# Polarshield_v2_0.net
KiCad netlist of a schematic drawn in EAGLE
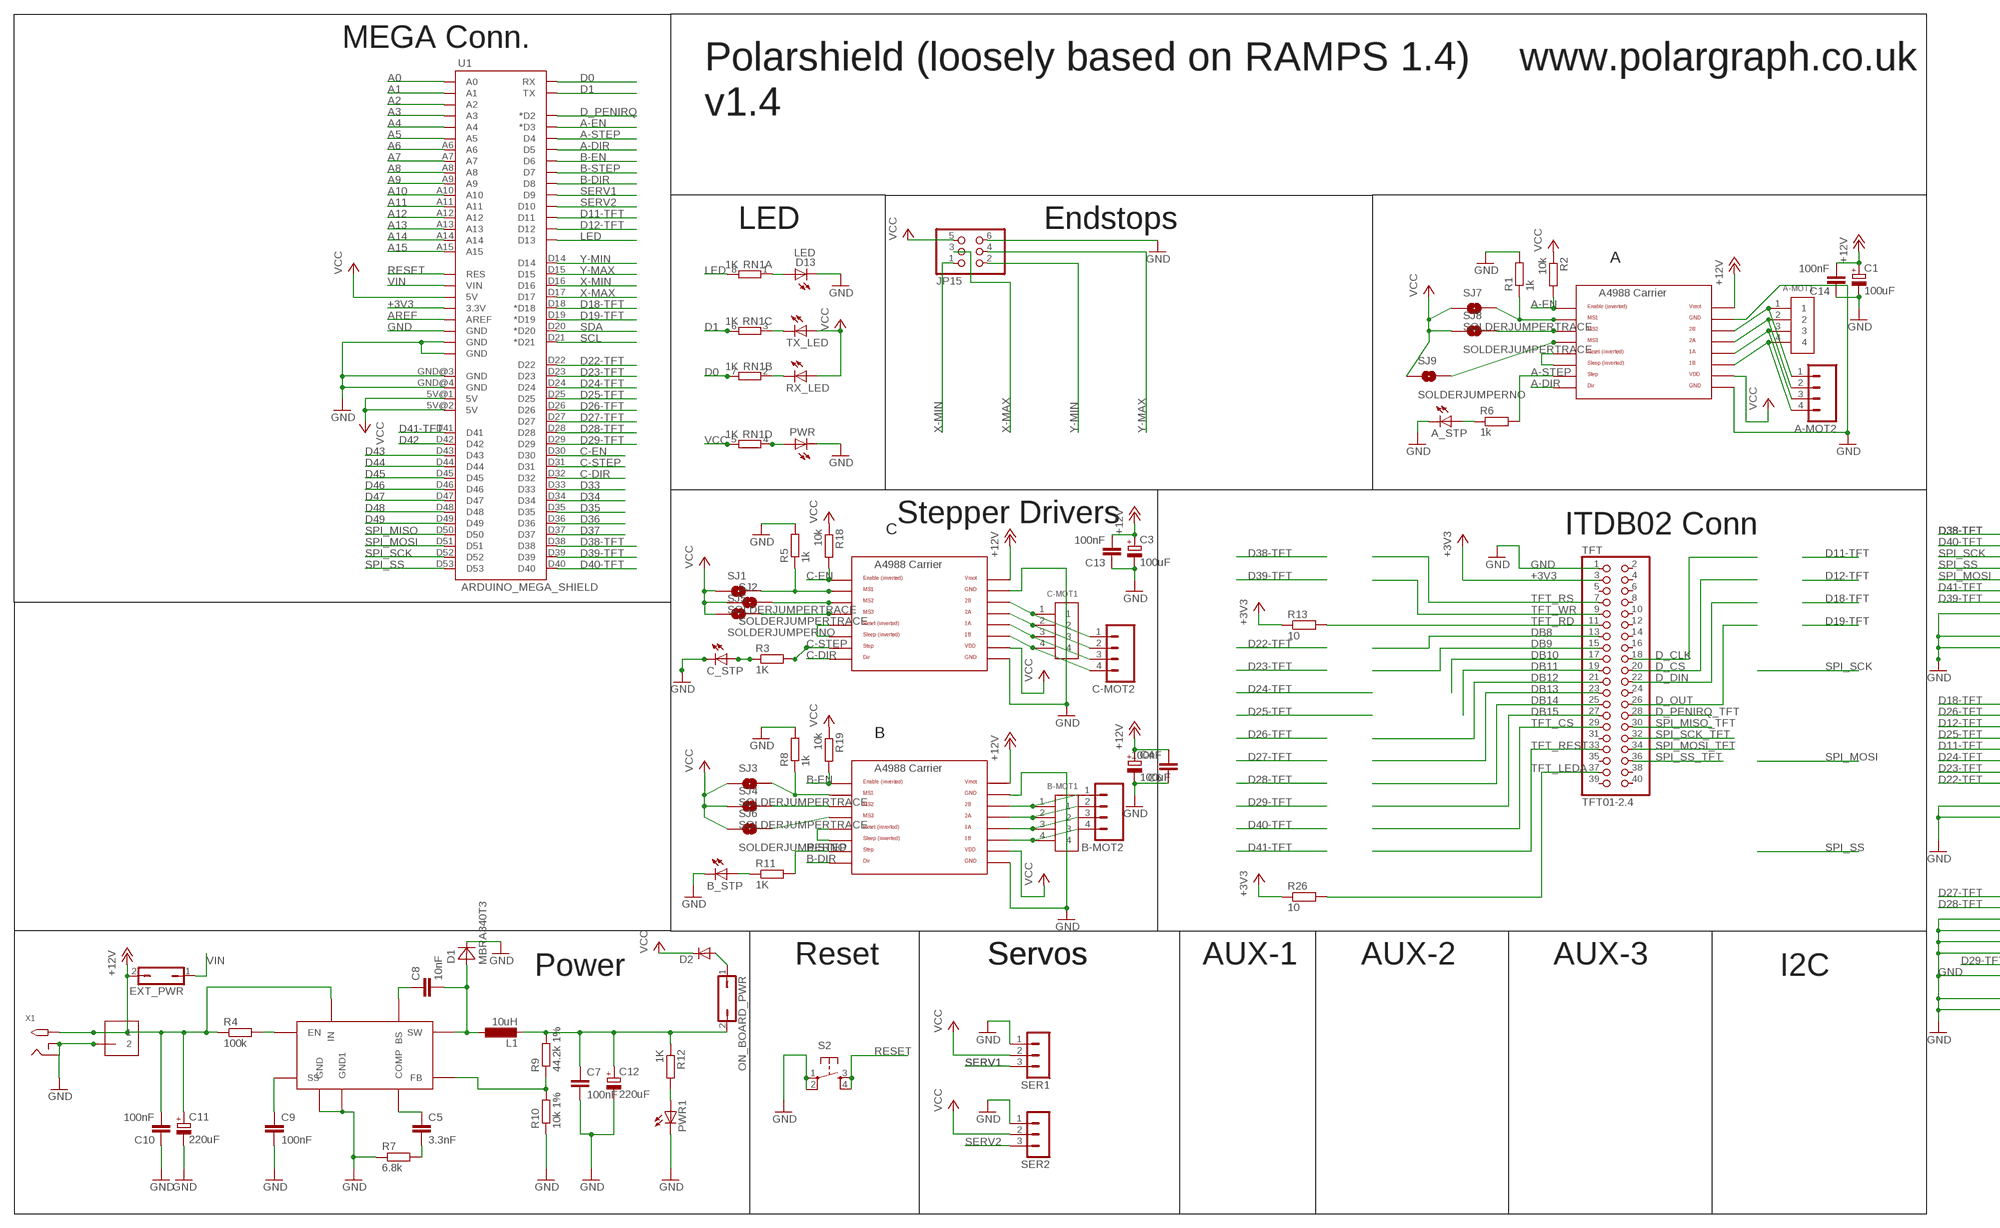
[diagram p0: schematic, sheet 1, part 1 of 2]
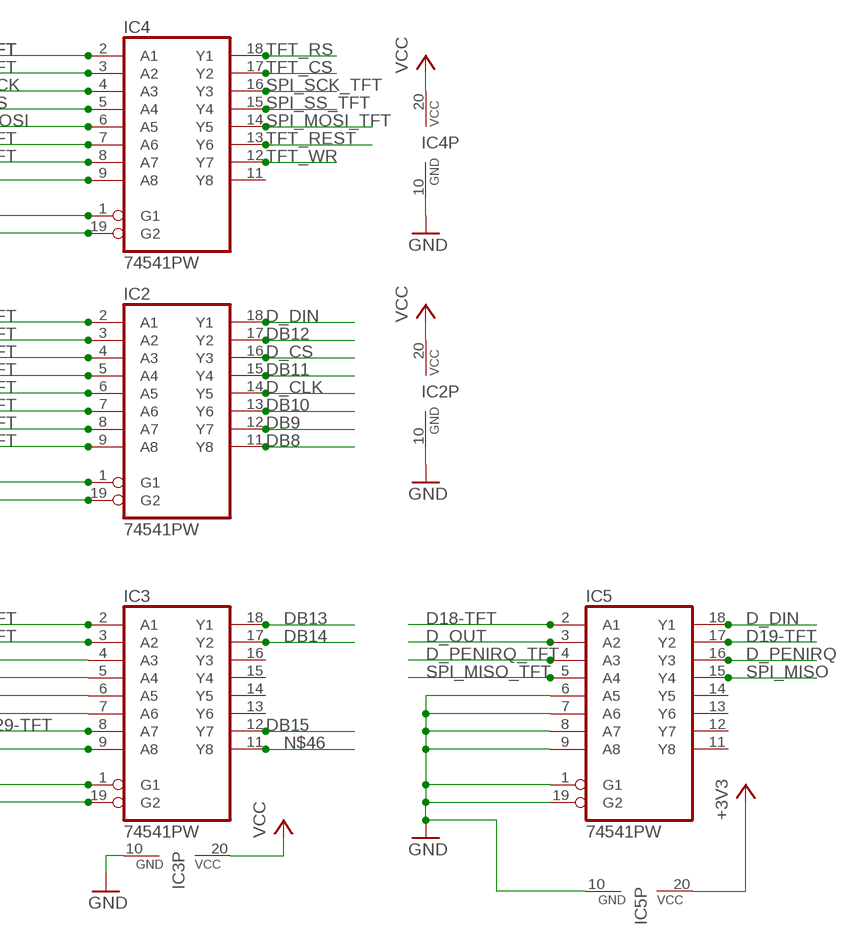
[diagram p1: schematic, sheet 1, part 2 of 2]

(export (version "E")
  (design (tool "Eeschema 10.0.6"))
  (components
    (comp (ref "A-MOT1")
      (value "1X4-BIG")
      (footprint "eagle-import:1X04-BIG")
      (libsource (lib "eagle-import") (part "1X4-BIG"))
    )
    (comp (ref "A-MOT2")
      (value "M04SCREW")
      (footprint "eagle-import:SCREWTERMINAL-3.5MM-4")
      (libsource (lib "eagle-import") (part "M04SCREW"))
    )
    (comp (ref "A_STP")
      (value "LEDCHIP-LED0805")
      (footprint "eagle-import:CHIP-LED0805")
      (libsource (lib "eagle-import") (part "LEDCHIP-LED0805"))
    )
    (comp (ref "B-MOT1")
      (value "1X4-BIG")
      (footprint "eagle-import:1X04-BIG")
      (libsource (lib "eagle-import") (part "1X4-BIG"))
    )
    (comp (ref "B-MOT2")
      (value "M04SCREW")
      (footprint "eagle-import:SCREWTERMINAL-3.5MM-4")
      (libsource (lib "eagle-import") (part "M04SCREW"))
    )
    (comp (ref "B_STP")
      (value "LEDCHIP-LED0805")
      (footprint "eagle-import:CHIP-LED0805")
      (libsource (lib "eagle-import") (part "LEDCHIP-LED0805"))
    )
    (comp (ref "C-MOT1")
      (value "1X4-BIG")
      (footprint "eagle-import:1X04-BIG")
      (libsource (lib "eagle-import") (part "1X4-BIG"))
    )
    (comp (ref "C-MOT2")
      (value "M04SCREW")
      (footprint "eagle-import:SCREWTERMINAL-3.5MM-4")
      (libsource (lib "eagle-import") (part "M04SCREW"))
    )
    (comp (ref "C1")
      (value "100uF")
      (footprint "eagle-import:153CLV-0605")
      (libsource (lib "eagle-import") (part "CPOL-EU153CLV-0605"))
    )
    (comp (ref "C3")
      (value "100uF")
      (footprint "eagle-import:153CLV-0605")
      (libsource (lib "eagle-import") (part "CPOL-EU153CLV-0605"))
    )
    (comp (ref "C4")
      (value "100uF")
      (footprint "eagle-import:153CLV-0605")
      (libsource (lib "eagle-import") (part "CPOL-EU153CLV-0605"))
    )
    (comp (ref "C5")
      (value "3.3nF")
      (footprint "eagle-import:C0805K")
      (libsource (lib "eagle-import") (part "C-EUC0805K"))
    )
    (comp (ref "C6")
      (value "100nF")
      (footprint "eagle-import:C0805")
      (libsource (lib "eagle-import") (part "C-EUC0805"))
    )
    (comp (ref "C7")
      (value "100nF")
      (footprint "eagle-import:C0805K")
      (libsource (lib "eagle-import") (part "C-EUC0805K"))
    )
    (comp (ref "C8")
      (value "10nF")
      (footprint "eagle-import:C0805K")
      (libsource (lib "eagle-import") (part "C-EUC0805K"))
    )
    (comp (ref "C9")
      (value "100nF")
      (footprint "eagle-import:C0805K")
      (libsource (lib "eagle-import") (part "C-EUC0805K"))
    )
    (comp (ref "C10")
      (value "100nF")
      (footprint "eagle-import:C0805K")
      (libsource (lib "eagle-import") (part "C-EUC0805K"))
    )
    (comp (ref "C11")
      (value "220uF")
      (footprint "eagle-import:153CLV-0807")
      (libsource (lib "eagle-import") (part "resistor_CPOL-EU153CLV-0807"))
    )
    (comp (ref "C12")
      (value "220uF")
      (footprint "eagle-import:153CLV-0807")
      (libsource (lib "eagle-import") (part "resistor_CPOL-EU153CLV-0807"))
    )
    (comp (ref "C13")
      (value "100nF")
      (footprint "eagle-import:C0805")
      (libsource (lib "eagle-import") (part "C-EUC0805"))
    )
    (comp (ref "C14")
      (value "100nF")
      (footprint "eagle-import:C0805")
      (libsource (lib "eagle-import") (part "C-EUC0805"))
    )
    (comp (ref "C_STP")
      (value "LEDCHIP-LED0805")
      (footprint "eagle-import:CHIP-LED0805")
      (libsource (lib "eagle-import") (part "LEDCHIP-LED0805"))
    )
    (comp (ref "D1")
      (value "MBRA340T3")
      (footprint "eagle-import:SMA")
      (libsource (lib "eagle-import") (part "MBRA340T3"))
    )
    (comp (ref "D2")
      (value "DIODE-DO214BA")
      (footprint "eagle-import:DO214BA")
      (libsource (lib "eagle-import") (part "DIODE-DO214BA"))
    )
    (comp (ref "D13")
      (value "LED")
      (footprint "eagle-import:CHIP-LED0805")
      (libsource (lib "eagle-import") (part "LEDCHIP-LED0805"))
    )
    (comp (ref "EXT_PWR")
      (value "JP1Q")
      (footprint "eagle-import:JP1")
      (libsource (lib "eagle-import") (part "JP1Q"))
    )
    (comp (ref "IC1")
      (value "MP2307")
      (footprint "eagle-import:SOIC8")
      (libsource (lib "eagle-import") (part "MP2307"))
    )
    (comp (ref "IC2")
      (value "74541PW")
      (footprint "eagle-import:TSSOP20")
      (libsource (lib "eagle-import") (part "74541PW"))
    )
    (comp (ref "IC3")
      (value "74541PW")
      (footprint "eagle-import:TSSOP20")
      (libsource (lib "eagle-import") (part "74541PW"))
    )
    (comp (ref "IC4")
      (value "74541PW")
      (footprint "eagle-import:TSSOP20")
      (libsource (lib "eagle-import") (part "74541PW"))
    )
    (comp (ref "IC5")
      (value "74541PW")
      (footprint "eagle-import:TSSOP20")
      (libsource (lib "eagle-import") (part "74541PW"))
    )
    (comp (ref "J1")
      (value "1X2-3.5MM")
      (footprint "eagle-import:1X2-3.5MM")
      (libsource (lib "eagle-import") (part "1X2-3.5MM"))
    )
    (comp (ref "JP15")
      (value "PINHD-2X3")
      (footprint "eagle-import:2X03")
      (libsource (lib "eagle-import") (part "PINHD-2X3"))
    )
    (comp (ref "L1")
      (value "10uH")
      (footprint "eagle-import:PIS2816")
      (libsource (lib "eagle-import") (part "L-EUPIS2816"))
    )
    (comp (ref "ON_BOARD_PWR")
      (value "JP1Q")
      (footprint "eagle-import:JP1")
      (libsource (lib "eagle-import") (part "JP1Q"))
    )
    (comp (ref "PWR")
      (value "LEDCHIP-LED0805")
      (footprint "eagle-import:CHIP-LED0805")
      (libsource (lib "eagle-import") (part "LEDCHIP-LED0805"))
    )
    (comp (ref "PWR1")
      (value "LEDCHIP-LED0805")
      (footprint "eagle-import:CHIP-LED0805")
      (libsource (lib "eagle-import") (part "LEDCHIP-LED0805"))
    )
    (comp (ref "R1")
      (value "1k")
      (footprint "eagle-import:R0805")
      (libsource (lib "eagle-import") (part "R-EU_R0805"))
    )
    (comp (ref "R2")
      (value "10k")
      (footprint "eagle-import:R0805")
      (libsource (lib "eagle-import") (part "R-EU_R0805"))
    )
    (comp (ref "R3")
      (value "1K")
      (footprint "eagle-import:R0805")
      (libsource (lib "eagle-import") (part "R-EU_R0805"))
    )
    (comp (ref "R4")
      (value "100k")
      (footprint "eagle-import:R0805")
      (libsource (lib "eagle-import") (part "resistor_R-EU_R0805"))
    )
    (comp (ref "R5")
      (value "1k")
      (footprint "eagle-import:R0805")
      (libsource (lib "eagle-import") (part "R-EU_R0805"))
    )
    (comp (ref "R6")
      (value "1k")
      (footprint "eagle-import:R0805")
      (libsource (lib "eagle-import") (part "R-EU_R0805"))
    )
    (comp (ref "R7")
      (value "6.8k")
      (footprint "eagle-import:R0805")
      (libsource (lib "eagle-import") (part "resistor_R-EU_R0805"))
    )
    (comp (ref "R8")
      (value "1k")
      (footprint "eagle-import:R0805")
      (libsource (lib "eagle-import") (part "R-EU_R0805"))
    )
    (comp (ref "R9")
      (value "44.2k 1%")
      (footprint "eagle-import:R0805")
      (libsource (lib "eagle-import") (part "resistor_R-EU_R0805"))
    )
    (comp (ref "R10")
      (value "10k 1%")
      (footprint "eagle-import:R0805")
      (libsource (lib "eagle-import") (part "resistor_R-EU_R0805"))
    )
    (comp (ref "R11")
      (value "1K")
      (footprint "eagle-import:R0805")
      (libsource (lib "eagle-import") (part "R-EU_R0805"))
    )
    (comp (ref "R12")
      (value "1K")
      (footprint "eagle-import:R0805")
      (libsource (lib "eagle-import") (part "R-EU_R0805"))
    )
    (comp (ref "R13")
      (value "10")
      (footprint "eagle-import:R0805")
      (libsource (lib "eagle-import") (part "resistor_R-EU_R0805"))
    )
    (comp (ref "R18")
      (value "10k")
      (footprint "eagle-import:R0805")
      (libsource (lib "eagle-import") (part "R-EU_R0805"))
    )
    (comp (ref "R19")
      (value "10k")
      (footprint "eagle-import:R0805")
      (libsource (lib "eagle-import") (part "R-EU_R0805"))
    )
    (comp (ref "R26")
      (value "10")
      (footprint "eagle-import:R0805")
      (libsource (lib "eagle-import") (part "resistor_R-EU_R0805"))
    )
    (comp (ref "RN1")
      (value "1K")
      (footprint "eagle-import:EXBS8V")
      (libsource (lib "eagle-import") (part "4R-NEXBS8V"))
    )
    (comp (ref "RX_LED")
      (value "LEDCHIP-LED0805")
      (footprint "eagle-import:CHIP-LED0805")
      (libsource (lib "eagle-import") (part "LEDCHIP-LED0805"))
    )
    (comp (ref "S2")
      (value "TAC_SWITCHPTH")
      (footprint "eagle-import:TACTILE-PTH")
      (libsource (lib "eagle-import") (part "TAC_SWITCHPTH"))
    )
    (comp (ref "SER1")
      (value "3PIN-HEADER")
      (footprint "eagle-import:3PIN-HEADER")
      (libsource (lib "eagle-import") (part "3PIN-HEADER"))
    )
    (comp (ref "SER2")
      (value "3PIN-HEADER")
      (footprint "eagle-import:3PIN-HEADER")
      (libsource (lib "eagle-import") (part "3PIN-HEADER"))
    )
    (comp (ref "SJ1")
      (value "SOLDERJUMPERTRACE")
      (footprint "eagle-import:SJ_2S-TRACE")
      (libsource (lib "eagle-import") (part "SOLDERJUMPERTRACE"))
    )
    (comp (ref "SJ2")
      (value "SOLDERJUMPERTRACE")
      (footprint "eagle-import:SJ_2S-TRACE")
      (libsource (lib "eagle-import") (part "SOLDERJUMPERTRACE"))
    )
    (comp (ref "SJ3")
      (value "SOLDERJUMPERTRACE")
      (footprint "eagle-import:SJ_2S-TRACE")
      (libsource (lib "eagle-import") (part "SOLDERJUMPERTRACE"))
    )
    (comp (ref "SJ4")
      (value "SOLDERJUMPERTRACE")
      (footprint "eagle-import:SJ_2S-TRACE")
      (libsource (lib "eagle-import") (part "SOLDERJUMPERTRACE"))
    )
    (comp (ref "SJ5")
      (value "SOLDERJUMPERNO")
      (footprint "eagle-import:SJ_2S-NO")
      (libsource (lib "eagle-import") (part "SOLDERJUMPERNO"))
    )
    (comp (ref "SJ6")
      (value "SOLDERJUMPERNO")
      (footprint "eagle-import:SJ_2S-NO")
      (libsource (lib "eagle-import") (part "SOLDERJUMPERNO"))
    )
    (comp (ref "SJ7")
      (value "SOLDERJUMPERTRACE")
      (footprint "eagle-import:SJ_2S-TRACE")
      (libsource (lib "eagle-import") (part "SOLDERJUMPERTRACE"))
    )
    (comp (ref "SJ8")
      (value "SOLDERJUMPERTRACE")
      (footprint "eagle-import:SJ_2S-TRACE")
      (libsource (lib "eagle-import") (part "SOLDERJUMPERTRACE"))
    )
    (comp (ref "SJ9")
      (value "SOLDERJUMPERNO")
      (footprint "eagle-import:SJ_2S-NO")
      (libsource (lib "eagle-import") (part "SOLDERJUMPERNO"))
    )
    (comp (ref "TFT")
      (value "TFT01-2.4")
      (footprint "eagle-import:TFT01-2.4")
      (libsource (lib "eagle-import") (part "TFT01-2.4"))
    )
    (comp (ref "TX_LED")
      (value "LEDCHIP-LED0805")
      (footprint "eagle-import:CHIP-LED0805")
      (libsource (lib "eagle-import") (part "LEDCHIP-LED0805"))
    )
    (comp (ref "U$1")
      (value "A4988BREAKOUT")
      (footprint "eagle-import:A4988BREAKOUT")
      (libsource (lib "eagle-import") (part "A4988BREAKOUT"))
    )
    (comp (ref "U$6")
      (value "A4988BREAKOUT")
      (footprint "eagle-import:A4988BREAKOUT")
      (libsource (lib "eagle-import") (part "A4988BREAKOUT"))
    )
    (comp (ref "U$7")
      (value "A4988BREAKOUT")
      (footprint "eagle-import:A4988BREAKOUT")
      (libsource (lib "eagle-import") (part "A4988BREAKOUT"))
    )
    (comp (ref "U1")
      (value "ARDUINO_MEGA_SHIELD")
      (footprint "eagle-import:ARDUINO_MEGA_SHIELD")
      (libsource (lib "eagle-import") (part "ARDUINO_MEGA_SHIELD"))
    )
    (comp (ref "X1")
      (value "2.1MMJACKTHM")
      (footprint "eagle-import:PJ-102A")
      (libsource (lib "eagle-import") (part "2.1MMJACKTHM"))
    )
  )
  (nets
    (net (code "1") (name "+3V3") (class "Default")
      (node (ref "IC5") (pin "20") (pinfunction "VCC_20") (pintype "power_in"))
      (node (ref "R13") (pin "1") (pinfunction "1_1") (pintype "passive"))
      (node (ref "R26") (pin "1") (pinfunction "1_1") (pintype "passive"))
      (node (ref "TFT") (pin "3") (pinfunction "3_3") (pintype "passive"))
      (node (ref "U1") (pin "3.3V") (pinfunction "3.3V_3.3V") (pintype "bidirectional"))
    )
    (net (code "2") (name "+12V") (class "Default")
      (node (ref "C1") (pin "+") (pinfunction "+_+") (pintype "passive"))
      (node (ref "C10") (pin "2") (pinfunction "2_2") (pintype "passive"))
      (node (ref "C11") (pin "+") (pinfunction "+_+") (pintype "passive"))
      (node (ref "C13") (pin "2") (pinfunction "2_2") (pintype "passive"))
      (node (ref "C14") (pin "2") (pinfunction "2_2") (pintype "passive"))
      (node (ref "C3") (pin "+") (pinfunction "+_+") (pintype "passive"))
      (node (ref "C4") (pin "+") (pinfunction "+_+") (pintype "passive"))
      (node (ref "C6") (pin "2") (pinfunction "2_2") (pintype "passive"))
      (node (ref "EXT_PWR") (pin "2") (pinfunction "2_2") (pintype "passive"))
      (node (ref "IC1") (pin "IN") (pinfunction "IN_IN") (pintype "bidirectional"))
      (node (ref "J1") (pin "1") (pinfunction "1_1") (pintype "passive"))
      (node (ref "R4") (pin "1") (pinfunction "1_1") (pintype "passive"))
      (node (ref "U$1") (pin "VMOT") (pinfunction "VMOT_VMOT") (pintype "power_in"))
      (node (ref "U$6") (pin "VMOT") (pinfunction "VMOT_VMOT") (pintype "power_in"))
      (node (ref "U$7") (pin "VMOT") (pinfunction "VMOT_VMOT") (pintype "power_in"))
      (node (ref "X1") (pin "TIP") (pinfunction "TIP_TIP") (pintype "bidirectional"))
    )
    (net (code "3") (name "/A-DIR") (class "Default")
      (node (ref "U$1") (pin "DIR") (pinfunction "DIR_DIR") (pintype "input"))
      (node (ref "U1") (pin "D5") (pinfunction "D5_D5") (pintype "bidirectional"))
    )
    (net (code "4") (name "/A-EN") (class "Default")
      (node (ref "R2") (pin "2") (pinfunction "2_2") (pintype "passive"))
      (node (ref "U$1") (pin "EN") (pinfunction "EN_EN") (pintype "input"))
      (node (ref "U1") (pin "D3") (pinfunction "*D3_D3") (pintype "bidirectional"))
    )
    (net (code "5") (name "/A-STEP") (class "Default")
      (node (ref "R6") (pin "2") (pinfunction "2_2") (pintype "passive"))
      (node (ref "U$1") (pin "STEP") (pinfunction "STEP_STEP") (pintype "input"))
      (node (ref "U1") (pin "D4") (pinfunction "D4_D4") (pintype "bidirectional"))
    )
    (net (code "6") (name "/A0") (class "Default")
      (node (ref "U1") (pin "A0") (pinfunction "A0_A0") (pintype "bidirectional"))
    )
    (net (code "7") (name "/A1") (class "Default")
      (node (ref "U1") (pin "A1") (pinfunction "A1_A1") (pintype "bidirectional"))
    )
    (net (code "8") (name "/A2") (class "Default")
      (node (ref "U1") (pin "A2") (pinfunction "A2_A2") (pintype "bidirectional"))
    )
    (net (code "9") (name "/A3") (class "Default")
      (node (ref "U1") (pin "A3") (pinfunction "A3_A3") (pintype "bidirectional"))
    )
    (net (code "10") (name "/A4") (class "Default")
      (node (ref "U1") (pin "A4") (pinfunction "A4_A4") (pintype "bidirectional"))
    )
    (net (code "11") (name "/A5") (class "Default")
      (node (ref "U1") (pin "A5") (pinfunction "A5_A5") (pintype "bidirectional"))
    )
    (net (code "12") (name "/A6") (class "Default")
      (node (ref "U1") (pin "A6") (pinfunction "A6_A6") (pintype "bidirectional"))
    )
    (net (code "13") (name "/A7") (class "Default")
      (node (ref "U1") (pin "A7") (pinfunction "A7_A7") (pintype "bidirectional"))
    )
    (net (code "14") (name "/A8") (class "Default")
      (node (ref "U1") (pin "A8") (pinfunction "A8_A8") (pintype "bidirectional"))
    )
    (net (code "15") (name "/A9") (class "Default")
      (node (ref "U1") (pin "A9") (pinfunction "A9_A9") (pintype "bidirectional"))
    )
    (net (code "16") (name "/A10") (class "Default")
      (node (ref "U1") (pin "A10") (pinfunction "A10_A10") (pintype "bidirectional"))
    )
    (net (code "17") (name "/A11") (class "Default")
      (node (ref "U1") (pin "A11") (pinfunction "A11_A11") (pintype "bidirectional"))
    )
    (net (code "18") (name "/A12") (class "Default")
      (node (ref "U1") (pin "A12") (pinfunction "A12_A12") (pintype "bidirectional"))
    )
    (net (code "19") (name "/A13") (class "Default")
      (node (ref "U1") (pin "A13") (pinfunction "A13_A13") (pintype "bidirectional"))
    )
    (net (code "20") (name "/A14") (class "Default")
      (node (ref "U1") (pin "A14") (pinfunction "A14_A14") (pintype "bidirectional"))
    )
    (net (code "21") (name "/A15") (class "Default")
      (node (ref "U1") (pin "A15") (pinfunction "A15_A15") (pintype "bidirectional"))
    )
    (net (code "22") (name "/AREF") (class "Default")
      (node (ref "U1") (pin "AREF") (pinfunction "AREF_AREF") (pintype "bidirectional"))
    )
    (net (code "23") (name "/B-DIR") (class "Default")
      (node (ref "U$7") (pin "DIR") (pinfunction "DIR_DIR") (pintype "input"))
      (node (ref "U1") (pin "D8") (pinfunction "D8_D8") (pintype "bidirectional"))
    )
    (net (code "24") (name "/B-EN") (class "Default")
      (node (ref "R19") (pin "2") (pinfunction "2_2") (pintype "passive"))
      (node (ref "U$7") (pin "EN") (pinfunction "EN_EN") (pintype "input"))
      (node (ref "U1") (pin "D6") (pinfunction "D6_D6") (pintype "bidirectional"))
    )
    (net (code "25") (name "/B-STEP") (class "Default")
      (node (ref "R11") (pin "2") (pinfunction "2_2") (pintype "passive"))
      (node (ref "U$7") (pin "STEP") (pinfunction "STEP_STEP") (pintype "input"))
      (node (ref "U1") (pin "D7") (pinfunction "D7_D7") (pintype "bidirectional"))
    )
    (net (code "26") (name "/C-DIR") (class "Default")
      (node (ref "U$6") (pin "DIR") (pinfunction "DIR_DIR") (pintype "input"))
      (node (ref "U1") (pin "D32") (pinfunction "D32_D32") (pintype "bidirectional"))
    )
    (net (code "27") (name "/C-EN") (class "Default")
      (node (ref "R18") (pin "2") (pinfunction "2_2") (pintype "passive"))
      (node (ref "U$6") (pin "EN") (pinfunction "EN_EN") (pintype "input"))
      (node (ref "U1") (pin "D30") (pinfunction "D30_D30") (pintype "bidirectional"))
    )
    (net (code "28") (name "/C-STEP") (class "Default")
      (node (ref "R3") (pin "2") (pinfunction "2_2") (pintype "passive"))
      (node (ref "U$6") (pin "STEP") (pinfunction "STEP_STEP") (pintype "input"))
      (node (ref "U1") (pin "D31") (pinfunction "D31_D31") (pintype "bidirectional"))
    )
    (net (code "29") (name "/D0") (class "Default")
      (node (ref "RN1") (pin "7") (pinfunction "2_7") (pintype "passive"))
      (node (ref "U1") (pin "RX") (pinfunction "RX_RX") (pintype "bidirectional"))
    )
    (net (code "30") (name "/D1") (class "Default")
      (node (ref "RN1") (pin "6") (pinfunction "2_6") (pintype "passive"))
      (node (ref "U1") (pin "TX") (pinfunction "TX_TX") (pintype "bidirectional"))
    )
    (net (code "31") (name "/D11-TFT") (class "Default")
      (node (ref "IC2") (pin "6") (pinfunction "A5_6") (pintype "input"))
      (node (ref "U1") (pin "D11") (pinfunction "D11_D11") (pintype "bidirectional"))
    )
    (net (code "32") (name "/D12-TFT") (class "Default")
      (node (ref "IC2") (pin "4") (pinfunction "A3_4") (pintype "input"))
      (node (ref "U1") (pin "D12") (pinfunction "D12_D12") (pintype "bidirectional"))
    )
    (net (code "33") (name "/D18-TFT") (class "Default")
      (node (ref "IC2") (pin "2") (pinfunction "A1_2") (pintype "input"))
      (node (ref "IC5") (pin "2") (pinfunction "A1_2") (pintype "input"))
      (node (ref "U1") (pin "D18") (pinfunction "*D18_D18") (pintype "bidirectional"))
    )
    (net (code "34") (name "/D19-TFT") (class "Default")
      (node (ref "IC5") (pin "17") (pinfunction "Y2_17") (pintype "tri_state"))
      (node (ref "U1") (pin "D19") (pinfunction "*D19_D19") (pintype "bidirectional"))
    )
    (net (code "35") (name "/D22-TFT") (class "Default")
      (node (ref "IC2") (pin "9") (pinfunction "A8_9") (pintype "input"))
      (node (ref "U1") (pin "D22") (pinfunction "D22_D22") (pintype "bidirectional"))
    )
    (net (code "36") (name "/D23-TFT") (class "Default")
      (node (ref "IC2") (pin "8") (pinfunction "A7_8") (pintype "input"))
      (node (ref "U1") (pin "D23") (pinfunction "D23_D23") (pintype "bidirectional"))
    )
    (net (code "37") (name "/D24-TFT") (class "Default")
      (node (ref "IC2") (pin "7") (pinfunction "A6_7") (pintype "input"))
      (node (ref "U1") (pin "D24") (pinfunction "D24_D24") (pintype "bidirectional"))
    )
    (net (code "38") (name "/D25-TFT") (class "Default")
      (node (ref "IC2") (pin "5") (pinfunction "A4_5") (pintype "input"))
      (node (ref "U1") (pin "D25") (pinfunction "D25_D25") (pintype "bidirectional"))
    )
    (net (code "39") (name "/D26-TFT") (class "Default")
      (node (ref "IC2") (pin "3") (pinfunction "A2_3") (pintype "input"))
      (node (ref "U1") (pin "D26") (pinfunction "D26_D26") (pintype "bidirectional"))
    )
    (net (code "40") (name "/D27-TFT") (class "Default")
      (node (ref "IC3") (pin "2") (pinfunction "A1_2") (pintype "input"))
      (node (ref "U1") (pin "D27") (pinfunction "D27_D27") (pintype "bidirectional"))
    )
    (net (code "41") (name "/D28-TFT") (class "Default")
      (node (ref "IC3") (pin "3") (pinfunction "A2_3") (pintype "input"))
      (node (ref "U1") (pin "D28") (pinfunction "D28_D28") (pintype "bidirectional"))
    )
    (net (code "42") (name "/D29-TFT") (class "Default")
      (node (ref "IC3") (pin "8") (pinfunction "A7_8") (pintype "input"))
      (node (ref "U1") (pin "D29") (pinfunction "D29_D29") (pintype "bidirectional"))
    )
    (net (code "43") (name "/D33") (class "Default")
      (node (ref "U1") (pin "D33") (pinfunction "D33_D33") (pintype "bidirectional"))
    )
    (net (code "44") (name "/D34") (class "Default")
      (node (ref "U1") (pin "D34") (pinfunction "D34_D34") (pintype "bidirectional"))
    )
    (net (code "45") (name "/D35") (class "Default")
      (node (ref "U1") (pin "D35") (pinfunction "D35_D35") (pintype "bidirectional"))
    )
    (net (code "46") (name "/D36") (class "Default")
      (node (ref "U1") (pin "D36") (pinfunction "D36_D36") (pintype "bidirectional"))
    )
    (net (code "47") (name "/D37") (class "Default")
      (node (ref "U1") (pin "D37") (pinfunction "D37_D37") (pintype "bidirectional"))
    )
    (net (code "48") (name "/D38-TFT") (class "Default")
      (node (ref "IC4") (pin "2") (pinfunction "A1_2") (pintype "input"))
      (node (ref "U1") (pin "D38") (pinfunction "D38_D38") (pintype "bidirectional"))
    )
    (net (code "49") (name "/D39-TFT") (class "Default")
      (node (ref "IC4") (pin "8") (pinfunction "A7_8") (pintype "input"))
      (node (ref "U1") (pin "D39") (pinfunction "D39_D39") (pintype "bidirectional"))
    )
    (net (code "50") (name "/D40-TFT") (class "Default")
      (node (ref "IC4") (pin "3") (pinfunction "A2_3") (pintype "input"))
      (node (ref "U1") (pin "D40") (pinfunction "D40_D40") (pintype "bidirectional"))
    )
    (net (code "51") (name "/D41-TFT") (class "Default")
      (node (ref "IC4") (pin "7") (pinfunction "A6_7") (pintype "input"))
      (node (ref "U1") (pin "D41") (pinfunction "D41_D41") (pintype "bidirectional"))
    )
    (net (code "52") (name "/D42") (class "Default")
      (node (ref "U1") (pin "D42") (pinfunction "D42_D42") (pintype "bidirectional"))
    )
    (net (code "53") (name "/D43") (class "Default")
      (node (ref "U1") (pin "D43") (pinfunction "D43_D43") (pintype "bidirectional"))
    )
    (net (code "54") (name "/D44") (class "Default")
      (node (ref "U1") (pin "D44") (pinfunction "D44_D44") (pintype "bidirectional"))
    )
    (net (code "55") (name "/D45") (class "Default")
      (node (ref "U1") (pin "D45") (pinfunction "D45_D45") (pintype "bidirectional"))
    )
    (net (code "56") (name "/D46") (class "Default")
      (node (ref "U1") (pin "D46") (pinfunction "D46_D46") (pintype "bidirectional"))
    )
    (net (code "57") (name "/D47") (class "Default")
      (node (ref "U1") (pin "D47") (pinfunction "D47_D47") (pintype "bidirectional"))
    )
    (net (code "58") (name "/D48") (class "Default")
      (node (ref "U1") (pin "D48") (pinfunction "D48_D48") (pintype "bidirectional"))
    )
    (net (code "59") (name "/D49") (class "Default")
      (node (ref "U1") (pin "D49") (pinfunction "D49_D49") (pintype "bidirectional"))
    )
    (net (code "60") (name "/DB8") (class "Default")
      (node (ref "IC2") (pin "11") (pinfunction "Y8_11") (pintype "tri_state"))
      (node (ref "TFT") (pin "13") (pinfunction "13_13") (pintype "passive"))
    )
    (net (code "61") (name "/DB9") (class "Default")
      (node (ref "IC2") (pin "12") (pinfunction "Y7_12") (pintype "tri_state"))
      (node (ref "TFT") (pin "15") (pinfunction "15_15") (pintype "passive"))
    )
    (net (code "62") (name "/DB10") (class "Default")
      (node (ref "IC2") (pin "13") (pinfunction "Y6_13") (pintype "tri_state"))
      (node (ref "TFT") (pin "17") (pinfunction "17_17") (pintype "passive"))
    )
    (net (code "63") (name "/DB11") (class "Default")
      (node (ref "IC2") (pin "15") (pinfunction "Y4_15") (pintype "tri_state"))
      (node (ref "TFT") (pin "19") (pinfunction "19_19") (pintype "passive"))
    )
    (net (code "64") (name "/DB12") (class "Default")
      (node (ref "IC2") (pin "17") (pinfunction "Y2_17") (pintype "tri_state"))
      (node (ref "TFT") (pin "21") (pinfunction "21_21") (pintype "passive"))
    )
    (net (code "65") (name "/DB13") (class "Default")
      (node (ref "IC3") (pin "18") (pinfunction "Y1_18") (pintype "tri_state"))
      (node (ref "TFT") (pin "23") (pinfunction "23_23") (pintype "passive"))
    )
    (net (code "66") (name "/DB14") (class "Default")
      (node (ref "IC3") (pin "17") (pinfunction "Y2_17") (pintype "tri_state"))
      (node (ref "TFT") (pin "25") (pinfunction "25_25") (pintype "passive"))
    )
    (net (code "67") (name "/DB15") (class "Default")
      (node (ref "IC3") (pin "12") (pinfunction "Y7_12") (pintype "tri_state"))
      (node (ref "TFT") (pin "27") (pinfunction "27_27") (pintype "passive"))
    )
    (net (code "68") (name "/D_CLK") (class "Default")
      (node (ref "IC2") (pin "14") (pinfunction "Y5_14") (pintype "tri_state"))
      (node (ref "TFT") (pin "18") (pinfunction "18_18") (pintype "passive"))
    )
    (net (code "69") (name "/D_CS") (class "Default")
      (node (ref "IC2") (pin "16") (pinfunction "Y3_16") (pintype "tri_state"))
      (node (ref "TFT") (pin "20") (pinfunction "20_20") (pintype "passive"))
    )
    (net (code "70") (name "/D_DIN") (class "Default")
      (node (ref "IC2") (pin "18") (pinfunction "Y1_18") (pintype "tri_state"))
      (node (ref "IC5") (pin "18") (pinfunction "Y1_18") (pintype "tri_state"))
      (node (ref "TFT") (pin "22") (pinfunction "22_22") (pintype "passive"))
    )
    (net (code "71") (name "/D_OUT") (class "Default")
      (node (ref "IC5") (pin "3") (pinfunction "A2_3") (pintype "input"))
      (node (ref "TFT") (pin "26") (pinfunction "26_26") (pintype "passive"))
    )
    (net (code "72") (name "/D_PENIRQ") (class "Default")
      (node (ref "IC5") (pin "16") (pinfunction "Y3_16") (pintype "tri_state"))
      (node (ref "U1") (pin "D2") (pinfunction "*D2_D2") (pintype "bidirectional"))
    )
    (net (code "73") (name "/D_PENIRQ_TFT") (class "Default")
      (node (ref "IC5") (pin "4") (pinfunction "A3_4") (pintype "input"))
      (node (ref "TFT") (pin "28") (pinfunction "28_28") (pintype "passive"))
    )
    (net (code "74") (name "/LED") (class "Default")
      (node (ref "RN1") (pin "8") (pinfunction "2_8") (pintype "passive"))
      (node (ref "U1") (pin "D13") (pinfunction "D13_D13") (pintype "bidirectional"))
    )
    (net (code "75") (name "/N$46") (class "Default")
      (node (ref "IC3") (pin "11") (pinfunction "Y8_11") (pintype "tri_state"))
    )
    (net (code "76") (name "/RESET") (class "Default")
      (node (ref "S2") (pin "3") (pinfunction "3_3") (pintype "passive"))
      (node (ref "S2") (pin "4") (pinfunction "4_4") (pintype "passive"))
      (node (ref "U1") (pin "RES") (pinfunction "RES_RES") (pintype "bidirectional"))
    )
    (net (code "77") (name "/SCL") (class "Default")
      (node (ref "U1") (pin "D21") (pinfunction "*D21_D21") (pintype "bidirectional"))
    )
    (net (code "78") (name "/SDA") (class "Default")
      (node (ref "U1") (pin "D20") (pinfunction "*D20_D20") (pintype "bidirectional"))
    )
    (net (code "79") (name "/SERV1") (class "Default")
      (node (ref "SER1") (pin "3") (pinfunction "3_3") (pintype "passive"))
      (node (ref "U1") (pin "D9") (pinfunction "D9_D9") (pintype "bidirectional"))
    )
    (net (code "80") (name "/SERV2") (class "Default")
      (node (ref "SER2") (pin "3") (pinfunction "3_3") (pintype "passive"))
      (node (ref "U1") (pin "D10") (pinfunction "D10_D10") (pintype "bidirectional"))
    )
    (net (code "81") (name "/SPI_MISO") (class "Default")
      (node (ref "IC5") (pin "15") (pinfunction "Y4_15") (pintype "tri_state"))
      (node (ref "U1") (pin "D50") (pinfunction "D50_D50") (pintype "bidirectional"))
    )
    (net (code "82") (name "/SPI_MISO_TFT") (class "Default")
      (node (ref "IC5") (pin "5") (pinfunction "A4_5") (pintype "input"))
      (node (ref "TFT") (pin "30") (pinfunction "30_30") (pintype "passive"))
    )
    (net (code "83") (name "/SPI_MOSI") (class "Default")
      (node (ref "IC4") (pin "6") (pinfunction "A5_6") (pintype "input"))
      (node (ref "U1") (pin "D51") (pinfunction "D51_D51") (pintype "bidirectional"))
    )
    (net (code "84") (name "/SPI_MOSI_TFT") (class "Default")
      (node (ref "IC4") (pin "14") (pinfunction "Y5_14") (pintype "tri_state"))
      (node (ref "TFT") (pin "34") (pinfunction "34_34") (pintype "passive"))
    )
    (net (code "85") (name "/SPI_SCK") (class "Default")
      (node (ref "IC4") (pin "4") (pinfunction "A3_4") (pintype "input"))
      (node (ref "U1") (pin "D52") (pinfunction "D52_D52") (pintype "bidirectional"))
    )
    (net (code "86") (name "/SPI_SCK_TFT") (class "Default")
      (node (ref "IC4") (pin "16") (pinfunction "Y3_16") (pintype "tri_state"))
      (node (ref "TFT") (pin "32") (pinfunction "32_32") (pintype "passive"))
    )
    (net (code "87") (name "/SPI_SS") (class "Default")
      (node (ref "IC4") (pin "5") (pinfunction "A4_5") (pintype "input"))
      (node (ref "U1") (pin "D53") (pinfunction "D53_D53") (pintype "bidirectional"))
    )
    (net (code "88") (name "/SPI_SS_TFT") (class "Default")
      (node (ref "IC4") (pin "15") (pinfunction "Y4_15") (pintype "tri_state"))
      (node (ref "TFT") (pin "36") (pinfunction "36_36") (pintype "passive"))
    )
    (net (code "89") (name "/TFT_CS") (class "Default")
      (node (ref "IC4") (pin "17") (pinfunction "Y2_17") (pintype "tri_state"))
      (node (ref "TFT") (pin "29") (pinfunction "29_29") (pintype "passive"))
    )
    (net (code "90") (name "/TFT_LEDA") (class "Default")
      (node (ref "R26") (pin "2") (pinfunction "2_2") (pintype "passive"))
      (node (ref "TFT") (pin "37") (pinfunction "37_37") (pintype "passive"))
    )
    (net (code "91") (name "/TFT_RD") (class "Default")
      (node (ref "R13") (pin "2") (pinfunction "2_2") (pintype "passive"))
      (node (ref "TFT") (pin "11") (pinfunction "11_11") (pintype "passive"))
    )
    (net (code "92") (name "/TFT_REST") (class "Default")
      (node (ref "IC4") (pin "13") (pinfunction "Y6_13") (pintype "tri_state"))
      (node (ref "TFT") (pin "33") (pinfunction "33_33") (pintype "passive"))
    )
    (net (code "93") (name "/TFT_RS") (class "Default")
      (node (ref "IC4") (pin "18") (pinfunction "Y1_18") (pintype "tri_state"))
      (node (ref "TFT") (pin "7") (pinfunction "7_7") (pintype "passive"))
    )
    (net (code "94") (name "/TFT_WR") (class "Default")
      (node (ref "IC4") (pin "12") (pinfunction "Y7_12") (pintype "tri_state"))
      (node (ref "TFT") (pin "9") (pinfunction "9_9") (pintype "passive"))
    )
    (net (code "95") (name "/VIN") (class "Default")
      (node (ref "EXT_PWR") (pin "1") (pinfunction "1_1") (pintype "passive"))
      (node (ref "U1") (pin "VIN") (pinfunction "VIN_VIN") (pintype "bidirectional"))
    )
    (net (code "96") (name "/X-MAX") (class "Default")
      (node (ref "JP15") (pin "3") (pinfunction "3_3") (pintype "passive"))
      (node (ref "U1") (pin "D17") (pinfunction "D17_D17") (pintype "bidirectional"))
    )
    (net (code "97") (name "/X-MIN") (class "Default")
      (node (ref "JP15") (pin "1") (pinfunction "1_1") (pintype "passive"))
      (node (ref "U1") (pin "D16") (pinfunction "D16_D16") (pintype "bidirectional"))
    )
    (net (code "98") (name "/Y-MAX") (class "Default")
      (node (ref "JP15") (pin "4") (pinfunction "4_4") (pintype "passive"))
      (node (ref "U1") (pin "D15") (pinfunction "D15_D15") (pintype "bidirectional"))
    )
    (net (code "99") (name "/Y-MIN") (class "Default")
      (node (ref "JP15") (pin "2") (pinfunction "2_2") (pintype "passive"))
      (node (ref "U1") (pin "D14") (pinfunction "D14_D14") (pintype "bidirectional"))
    )
    (net (code "100") (name "GND") (class "Default")
      (node (ref "A_STP") (pin "C") (pinfunction "C_C") (pintype "passive"))
      (node (ref "B_STP") (pin "C") (pinfunction "C_C") (pintype "passive"))
      (node (ref "C1") (pin "-") (pinfunction "-_-") (pintype "passive"))
      (node (ref "C10") (pin "1") (pinfunction "1_1") (pintype "passive"))
      (node (ref "C11") (pin "-") (pinfunction "-_-") (pintype "passive"))
      (node (ref "C12") (pin "-") (pinfunction "-_-") (pintype "passive"))
      (node (ref "C13") (pin "1") (pinfunction "1_1") (pintype "passive"))
      (node (ref "C14") (pin "1") (pinfunction "1_1") (pintype "passive"))
      (node (ref "C3") (pin "-") (pinfunction "-_-") (pintype "passive"))
      (node (ref "C4") (pin "-") (pinfunction "-_-") (pintype "passive"))
      (node (ref "C6") (pin "1") (pinfunction "1_1") (pintype "passive"))
      (node (ref "C7") (pin "2") (pinfunction "2_2") (pintype "passive"))
      (node (ref "C9") (pin "2") (pinfunction "2_2") (pintype "passive"))
      (node (ref "C_STP") (pin "C") (pinfunction "C_C") (pintype "passive"))
      (node (ref "D1") (pin "C") (pinfunction "C_C") (pintype "passive"))
      (node (ref "D13") (pin "C") (pinfunction "C_C") (pintype "passive"))
      (node (ref "IC1") (pin "GND") (pinfunction "GND_GND") (pintype "bidirectional"))
      (node (ref "IC1") (pin "GND1") (pinfunction "GND1_GND1") (pintype "bidirectional"))
      (node (ref "IC2") (pin "1") (pinfunction "G1_1") (pintype "input"))
      (node (ref "IC2") (pin "10") (pinfunction "GND_10") (pintype "power_in"))
      (node (ref "IC2") (pin "19") (pinfunction "G2_19") (pintype "input"))
      (node (ref "IC3") (pin "1") (pinfunction "G1_1") (pintype "input"))
      (node (ref "IC3") (pin "10") (pinfunction "GND_10") (pintype "power_in"))
      (node (ref "IC3") (pin "19") (pinfunction "G2_19") (pintype "input"))
      (node (ref "IC3") (pin "4") (pinfunction "A3_4") (pintype "input"))
      (node (ref "IC3") (pin "5") (pinfunction "A4_5") (pintype "input"))
      (node (ref "IC3") (pin "6") (pinfunction "A5_6") (pintype "input"))
      (node (ref "IC3") (pin "7") (pinfunction "A6_7") (pintype "input"))
      (node (ref "IC3") (pin "9") (pinfunction "A8_9") (pintype "input"))
      (node (ref "IC4") (pin "1") (pinfunction "G1_1") (pintype "input"))
      (node (ref "IC4") (pin "10") (pinfunction "GND_10") (pintype "power_in"))
      (node (ref "IC4") (pin "19") (pinfunction "G2_19") (pintype "input"))
      (node (ref "IC4") (pin "9") (pinfunction "A8_9") (pintype "input"))
      (node (ref "IC5") (pin "1") (pinfunction "G1_1") (pintype "input"))
      (node (ref "IC5") (pin "10") (pinfunction "GND_10") (pintype "power_in"))
      (node (ref "IC5") (pin "19") (pinfunction "G2_19") (pintype "input"))
      (node (ref "IC5") (pin "6") (pinfunction "A5_6") (pintype "input"))
      (node (ref "IC5") (pin "7") (pinfunction "A6_7") (pintype "input"))
      (node (ref "IC5") (pin "8") (pinfunction "A7_8") (pintype "input"))
      (node (ref "IC5") (pin "9") (pinfunction "A8_9") (pintype "input"))
      (node (ref "J1") (pin "2") (pinfunction "2_2") (pintype "passive"))
      (node (ref "JP15") (pin "6") (pinfunction "6_6") (pintype "passive"))
      (node (ref "PWR") (pin "C") (pinfunction "C_C") (pintype "passive"))
      (node (ref "PWR1") (pin "C") (pinfunction "C_C") (pintype "passive"))
      (node (ref "R1") (pin "2") (pinfunction "2_2") (pintype "passive"))
      (node (ref "R10") (pin "1") (pinfunction "1_1") (pintype "passive"))
      (node (ref "R5") (pin "2") (pinfunction "2_2") (pintype "passive"))
      (node (ref "R7") (pin "1") (pinfunction "1_1") (pintype "passive"))
      (node (ref "R8") (pin "2") (pinfunction "2_2") (pintype "passive"))
      (node (ref "S2") (pin "1") (pinfunction "1_1") (pintype "passive"))
      (node (ref "S2") (pin "2") (pinfunction "2_2") (pintype "passive"))
      (node (ref "SER1") (pin "1") (pinfunction "1_1") (pintype "passive"))
      (node (ref "SER2") (pin "1") (pinfunction "1_1") (pintype "passive"))
      (node (ref "TFT") (pin "1") (pinfunction "1_1") (pintype "passive"))
      (node (ref "U$1") (pin "GND") (pinfunction "GND_GND") (pintype "power_in"))
      (node (ref "U$1") (pin "GND@0") (pinfunction "GND_GND@0") (pintype "power_in"))
      (node (ref "U$6") (pin "GND") (pinfunction "GND_GND") (pintype "power_in"))
      (node (ref "U$6") (pin "GND@0") (pinfunction "GND_GND@0") (pintype "power_in"))
      (node (ref "U$7") (pin "GND") (pinfunction "GND_GND") (pintype "power_in"))
      (node (ref "U$7") (pin "GND@0") (pinfunction "GND_GND@0") (pintype "power_in"))
      (node (ref "U1") (pin "GND@0") (pinfunction "GND_GND@0") (pintype "power_in"))
      (node (ref "U1") (pin "GND@1") (pinfunction "GND_GND@1") (pintype "power_in"))
      (node (ref "U1") (pin "GND@2") (pinfunction "GND_GND@2") (pintype "power_in"))
      (node (ref "U1") (pin "GND@3") (pinfunction "GND_GND@3") (pintype "power_in"))
      (node (ref "U1") (pin "GND@4") (pinfunction "GND_GND@4") (pintype "power_in"))
      (node (ref "X1") (pin "RING") (pinfunction "RING_RING") (pintype "bidirectional"))
      (node (ref "X1") (pin "RING_SW") (pinfunction "RING_SW_RING_SW") (pintype "bidirectional"))
    )
    (net (code "101") (name "Net-(A-MOT1-Pad1)") (class "Default")
      (node (ref "A-MOT1") (pin "1") (pinfunction "1_1") (pintype "bidirectional"))
      (node (ref "A-MOT2") (pin "1") (pinfunction "1_1") (pintype "passive"))
      (node (ref "U$1") (pin "2B") (pinfunction "2B_2B") (pintype "output"))
    )
    (net (code "102") (name "Net-(A-MOT1-Pad2)") (class "Default")
      (node (ref "A-MOT1") (pin "2") (pinfunction "2_2") (pintype "bidirectional"))
      (node (ref "A-MOT2") (pin "2") (pinfunction "2_2") (pintype "passive"))
      (node (ref "U$1") (pin "2A") (pinfunction "2A_2A") (pintype "output"))
    )
    (net (code "103") (name "Net-(A-MOT1-Pad3)") (class "Default")
      (node (ref "A-MOT1") (pin "3") (pinfunction "3_3") (pintype "bidirectional"))
      (node (ref "A-MOT2") (pin "3") (pinfunction "3_3") (pintype "passive"))
      (node (ref "U$1") (pin "1A") (pinfunction "1A_1A") (pintype "output"))
    )
    (net (code "104") (name "Net-(A-MOT1-Pad4)") (class "Default")
      (node (ref "A-MOT1") (pin "4") (pinfunction "4_4") (pintype "bidirectional"))
      (node (ref "A-MOT2") (pin "4") (pinfunction "4_4") (pintype "passive"))
      (node (ref "U$1") (pin "1B") (pinfunction "1B_1B") (pintype "output"))
    )
    (net (code "105") (name "Net-(A_STP-PadA)") (class "Default")
      (node (ref "A_STP") (pin "A") (pinfunction "A_A") (pintype "passive"))
      (node (ref "R6") (pin "1") (pinfunction "1_1") (pintype "passive"))
    )
    (net (code "106") (name "Net-(B-MOT1-Pad1)") (class "Default")
      (node (ref "B-MOT1") (pin "1") (pinfunction "1_1") (pintype "bidirectional"))
      (node (ref "B-MOT2") (pin "1") (pinfunction "1_1") (pintype "passive"))
      (node (ref "U$7") (pin "2B") (pinfunction "2B_2B") (pintype "output"))
    )
    (net (code "107") (name "Net-(B-MOT1-Pad2)") (class "Default")
      (node (ref "B-MOT1") (pin "2") (pinfunction "2_2") (pintype "bidirectional"))
      (node (ref "B-MOT2") (pin "2") (pinfunction "2_2") (pintype "passive"))
      (node (ref "U$7") (pin "2A") (pinfunction "2A_2A") (pintype "output"))
    )
    (net (code "108") (name "Net-(B-MOT1-Pad3)") (class "Default")
      (node (ref "B-MOT1") (pin "3") (pinfunction "3_3") (pintype "bidirectional"))
      (node (ref "B-MOT2") (pin "3") (pinfunction "3_3") (pintype "passive"))
      (node (ref "U$7") (pin "1A") (pinfunction "1A_1A") (pintype "output"))
    )
    (net (code "109") (name "Net-(B-MOT1-Pad4)") (class "Default")
      (node (ref "B-MOT1") (pin "4") (pinfunction "4_4") (pintype "bidirectional"))
      (node (ref "B-MOT2") (pin "4") (pinfunction "4_4") (pintype "passive"))
      (node (ref "U$7") (pin "1B") (pinfunction "1B_1B") (pintype "output"))
    )
    (net (code "110") (name "Net-(B_STP-PadA)") (class "Default")
      (node (ref "B_STP") (pin "A") (pinfunction "A_A") (pintype "passive"))
      (node (ref "R11") (pin "1") (pinfunction "1_1") (pintype "passive"))
    )
    (net (code "111") (name "Net-(C-MOT1-Pad1)") (class "Default")
      (node (ref "C-MOT1") (pin "1") (pinfunction "1_1") (pintype "bidirectional"))
      (node (ref "C-MOT2") (pin "1") (pinfunction "1_1") (pintype "passive"))
      (node (ref "U$6") (pin "2B") (pinfunction "2B_2B") (pintype "output"))
    )
    (net (code "112") (name "Net-(C-MOT1-Pad2)") (class "Default")
      (node (ref "C-MOT1") (pin "2") (pinfunction "2_2") (pintype "bidirectional"))
      (node (ref "C-MOT2") (pin "2") (pinfunction "2_2") (pintype "passive"))
      (node (ref "U$6") (pin "2A") (pinfunction "2A_2A") (pintype "output"))
    )
    (net (code "113") (name "Net-(C-MOT1-Pad3)") (class "Default")
      (node (ref "C-MOT1") (pin "3") (pinfunction "3_3") (pintype "bidirectional"))
      (node (ref "C-MOT2") (pin "3") (pinfunction "3_3") (pintype "passive"))
      (node (ref "U$6") (pin "1A") (pinfunction "1A_1A") (pintype "output"))
    )
    (net (code "114") (name "Net-(C-MOT1-Pad4)") (class "Default")
      (node (ref "C-MOT1") (pin "4") (pinfunction "4_4") (pintype "bidirectional"))
      (node (ref "C-MOT2") (pin "4") (pinfunction "4_4") (pintype "passive"))
      (node (ref "U$6") (pin "1B") (pinfunction "1B_1B") (pintype "output"))
    )
    (net (code "115") (name "Net-(C5-Pad1)") (class "Default")
      (node (ref "C5") (pin "1") (pinfunction "1_1") (pintype "passive"))
      (node (ref "IC1") (pin "COMP") (pinfunction "COMP_COMP") (pintype "bidirectional"))
    )
    (net (code "116") (name "Net-(C5-Pad2)") (class "Default")
      (node (ref "C5") (pin "2") (pinfunction "2_2") (pintype "passive"))
      (node (ref "R7") (pin "2") (pinfunction "2_2") (pintype "passive"))
    )
    (net (code "117") (name "Net-(C8-Pad1)") (class "Default")
      (node (ref "C8") (pin "1") (pinfunction "1_1") (pintype "passive"))
      (node (ref "IC1") (pin "BS") (pinfunction "BS_BS") (pintype "bidirectional"))
    )
    (net (code "118") (name "Net-(C8-Pad2)") (class "Default")
      (node (ref "C8") (pin "2") (pinfunction "2_2") (pintype "passive"))
      (node (ref "D1") (pin "A") (pinfunction "A_A") (pintype "passive"))
      (node (ref "IC1") (pin "SW") (pinfunction "SW_SW") (pintype "bidirectional"))
      (node (ref "L1") (pin "1") (pinfunction "1_1") (pintype "passive"))
    )
    (net (code "119") (name "Net-(C9-Pad1)") (class "Default")
      (node (ref "C9") (pin "1") (pinfunction "1_1") (pintype "passive"))
      (node (ref "IC1") (pin "SS") (pinfunction "SS_SS") (pintype "bidirectional"))
    )
    (net (code "120") (name "Net-(C12-Pad+)") (class "Default")
      (node (ref "C12") (pin "+") (pinfunction "+_+") (pintype "passive"))
      (node (ref "C7") (pin "1") (pinfunction "1_1") (pintype "passive"))
      (node (ref "L1") (pin "2") (pinfunction "2_2") (pintype "passive"))
      (node (ref "ON_BOARD_PWR") (pin "2") (pinfunction "2_2") (pintype "passive"))
      (node (ref "R12") (pin "1") (pinfunction "1_1") (pintype "passive"))
      (node (ref "R9") (pin "2") (pinfunction "2_2") (pintype "passive"))
    )
    (net (code "121") (name "Net-(C_STP-PadA)") (class "Default")
      (node (ref "C_STP") (pin "A") (pinfunction "A_A") (pintype "passive"))
      (node (ref "R3") (pin "1") (pinfunction "1_1") (pintype "passive"))
    )
    (net (code "122") (name "Net-(D2-PadA)") (class "Default")
      (node (ref "D2") (pin "A") (pinfunction "A_A") (pintype "passive"))
      (node (ref "ON_BOARD_PWR") (pin "1") (pinfunction "1_1") (pintype "passive"))
    )
    (net (code "123") (name "Net-(D13-PadA)") (class "Default")
      (node (ref "D13") (pin "A") (pinfunction "A_A") (pintype "passive"))
      (node (ref "RN1") (pin "1") (pinfunction "1_1") (pintype "passive"))
    )
    (net (code "124") (name "Net-(IC1-PadEN)") (class "Default")
      (node (ref "IC1") (pin "EN") (pinfunction "EN_EN") (pintype "bidirectional"))
      (node (ref "R4") (pin "2") (pinfunction "2_2") (pintype "passive"))
    )
    (net (code "125") (name "Net-(IC1-PadFB)") (class "Default")
      (node (ref "IC1") (pin "FB") (pinfunction "FB_FB") (pintype "bidirectional"))
      (node (ref "R10") (pin "2") (pinfunction "2_2") (pintype "passive"))
      (node (ref "R9") (pin "1") (pinfunction "1_1") (pintype "passive"))
    )
    (net (code "126") (name "Net-(PWR1-PadA)") (class "Default")
      (node (ref "PWR1") (pin "A") (pinfunction "A_A") (pintype "passive"))
      (node (ref "R12") (pin "2") (pinfunction "2_2") (pintype "passive"))
    )
    (net (code "127") (name "Net-(R1-Pad1)") (class "Default")
      (node (ref "R1") (pin "1") (pinfunction "1_1") (pintype "passive"))
      (node (ref "SJ7") (pin "2") (pinfunction "2_2") (pintype "passive"))
      (node (ref "U$1") (pin "MS1") (pinfunction "MS1_MS1") (pintype "input"))
    )
    (net (code "128") (name "Net-(R5-Pad1)") (class "Default")
      (node (ref "R5") (pin "1") (pinfunction "1_1") (pintype "passive"))
      (node (ref "SJ1") (pin "2") (pinfunction "2_2") (pintype "passive"))
      (node (ref "U$6") (pin "MS1") (pinfunction "MS1_MS1") (pintype "input"))
    )
    (net (code "129") (name "Net-(R8-Pad1)") (class "Default")
      (node (ref "R8") (pin "1") (pinfunction "1_1") (pintype "passive"))
      (node (ref "SJ3") (pin "2") (pinfunction "2_2") (pintype "passive"))
      (node (ref "U$7") (pin "MS1") (pinfunction "MS1_MS1") (pintype "input"))
    )
    (net (code "130") (name "Net-(RN1B-1)") (class "Default")
      (node (ref "RN1") (pin "2") (pinfunction "1_2") (pintype "passive"))
      (node (ref "RX_LED") (pin "C") (pinfunction "C_C") (pintype "passive"))
    )
    (net (code "131") (name "Net-(RN1C-1)") (class "Default")
      (node (ref "RN1") (pin "3") (pinfunction "1_3") (pintype "passive"))
      (node (ref "TX_LED") (pin "C") (pinfunction "C_C") (pintype "passive"))
    )
    (net (code "132") (name "Net-(RN1D-1)") (class "Default")
      (node (ref "PWR") (pin "A") (pinfunction "A_A") (pintype "passive"))
      (node (ref "RN1") (pin "4") (pinfunction "1_4") (pintype "passive"))
    )
    (net (code "133") (name "Net-(SJ2-Pad2)") (class "Default")
      (node (ref "SJ2") (pin "2") (pinfunction "2_2") (pintype "passive"))
      (node (ref "U$6") (pin "MS2") (pinfunction "MS2_MS2") (pintype "input"))
    )
    (net (code "134") (name "Net-(SJ4-Pad2)") (class "Default")
      (node (ref "SJ4") (pin "2") (pinfunction "2_2") (pintype "passive"))
      (node (ref "U$7") (pin "MS2") (pinfunction "MS2_MS2") (pintype "input"))
    )
    (net (code "135") (name "Net-(SJ5-Pad2)") (class "Default")
      (node (ref "SJ5") (pin "2") (pinfunction "2_2") (pintype "passive"))
      (node (ref "U$6") (pin "MS3") (pinfunction "MS3_MS3") (pintype "input"))
    )
    (net (code "136") (name "Net-(SJ6-Pad2)") (class "Default")
      (node (ref "SJ6") (pin "2") (pinfunction "2_2") (pintype "passive"))
      (node (ref "U$7") (pin "MS3") (pinfunction "MS3_MS3") (pintype "input"))
    )
    (net (code "137") (name "Net-(SJ8-Pad2)") (class "Default")
      (node (ref "SJ8") (pin "2") (pinfunction "2_2") (pintype "passive"))
      (node (ref "U$1") (pin "MS2") (pinfunction "MS2_MS2") (pintype "input"))
    )
    (net (code "138") (name "Net-(SJ9-Pad2)") (class "Default")
      (node (ref "SJ9") (pin "2") (pinfunction "2_2") (pintype "passive"))
      (node (ref "U$1") (pin "MS3") (pinfunction "MS3_MS3") (pintype "input"))
    )
    (net (code "139") (name "Net-(U$1-SLEEP)") (class "Default")
      (node (ref "U$1") (pin "RST") (pinfunction "RST_RST") (pintype "input"))
      (node (ref "U$1") (pin "SLP") (pinfunction "SLEEP_SLP") (pintype "input"))
    )
    (net (code "140") (name "Net-(U$6-SLEEP)") (class "Default")
      (node (ref "U$6") (pin "RST") (pinfunction "RST_RST") (pintype "input"))
      (node (ref "U$6") (pin "SLP") (pinfunction "SLEEP_SLP") (pintype "input"))
    )
    (net (code "141") (name "Net-(U$7-SLEEP)") (class "Default")
      (node (ref "U$7") (pin "RST") (pinfunction "RST_RST") (pintype "input"))
      (node (ref "U$7") (pin "SLP") (pinfunction "SLEEP_SLP") (pintype "input"))
    )
    (net (code "142") (name "VCC") (class "Default")
      (node (ref "D2") (pin "C") (pinfunction "C_C") (pintype "passive"))
      (node (ref "IC2") (pin "20") (pinfunction "VCC_20") (pintype "power_in"))
      (node (ref "IC3") (pin "20") (pinfunction "VCC_20") (pintype "power_in"))
      (node (ref "IC4") (pin "20") (pinfunction "VCC_20") (pintype "power_in"))
      (node (ref "JP15") (pin "5") (pinfunction "5_5") (pintype "passive"))
      (node (ref "R18") (pin "1") (pinfunction "1_1") (pintype "passive"))
      (node (ref "R19") (pin "1") (pinfunction "1_1") (pintype "passive"))
      (node (ref "R2") (pin "1") (pinfunction "1_1") (pintype "passive"))
      (node (ref "RN1") (pin "5") (pinfunction "2_5") (pintype "passive"))
      (node (ref "RX_LED") (pin "A") (pinfunction "A_A") (pintype "passive"))
      (node (ref "SER1") (pin "2") (pinfunction "2_2") (pintype "passive"))
      (node (ref "SER2") (pin "2") (pinfunction "2_2") (pintype "passive"))
      (node (ref "SJ1") (pin "1") (pinfunction "1_1") (pintype "passive"))
      (node (ref "SJ2") (pin "1") (pinfunction "1_1") (pintype "passive"))
      (node (ref "SJ3") (pin "1") (pinfunction "1_1") (pintype "passive"))
      (node (ref "SJ4") (pin "1") (pinfunction "1_1") (pintype "passive"))
      (node (ref "SJ5") (pin "1") (pinfunction "1_1") (pintype "passive"))
      (node (ref "SJ6") (pin "1") (pinfunction "1_1") (pintype "passive"))
      (node (ref "SJ7") (pin "1") (pinfunction "1_1") (pintype "passive"))
      (node (ref "SJ8") (pin "1") (pinfunction "1_1") (pintype "passive"))
      (node (ref "SJ9") (pin "1") (pinfunction "1_1") (pintype "passive"))
      (node (ref "TX_LED") (pin "A") (pinfunction "A_A") (pintype "passive"))
      (node (ref "U$1") (pin "VDD") (pinfunction "VDD_VDD") (pintype "power_in"))
      (node (ref "U$6") (pin "VDD") (pinfunction "VDD_VDD") (pintype "power_in"))
      (node (ref "U$7") (pin "VDD") (pinfunction "VDD_VDD") (pintype "power_in"))
      (node (ref "U1") (pin "5V@0") (pinfunction "5V_5V@0") (pintype "power_in"))
      (node (ref "U1") (pin "5V@1") (pinfunction "5V_5V@1") (pintype "power_in"))
      (node (ref "U1") (pin "5V@2") (pinfunction "5V_5V@2") (pintype "power_in"))
    )
    (net (code "143") (name "unconnected-(IC3A-Y3-Pad16)") (class "Default")
      (node (ref "IC3") (pin "16") (pinfunction "Y3_16") (pintype "tri_state"))
    )
    (net (code "144") (name "unconnected-(IC3A-Y4-Pad15)") (class "Default")
      (node (ref "IC3") (pin "15") (pinfunction "Y4_15") (pintype "tri_state"))
    )
    (net (code "145") (name "unconnected-(IC3A-Y5-Pad14)") (class "Default")
      (node (ref "IC3") (pin "14") (pinfunction "Y5_14") (pintype "tri_state"))
    )
    (net (code "146") (name "unconnected-(IC3A-Y6-Pad13)") (class "Default")
      (node (ref "IC3") (pin "13") (pinfunction "Y6_13") (pintype "tri_state"))
    )
    (net (code "147") (name "unconnected-(IC4A-Y8-Pad11)") (class "Default")
      (node (ref "IC4") (pin "11") (pinfunction "Y8_11") (pintype "tri_state"))
    )
    (net (code "148") (name "unconnected-(IC5A-Y5-Pad14)") (class "Default")
      (node (ref "IC5") (pin "14") (pinfunction "Y5_14") (pintype "tri_state"))
    )
    (net (code "149") (name "unconnected-(IC5A-Y6-Pad13)") (class "Default")
      (node (ref "IC5") (pin "13") (pinfunction "Y6_13") (pintype "tri_state"))
    )
    (net (code "150") (name "unconnected-(IC5A-Y7-Pad12)") (class "Default")
      (node (ref "IC5") (pin "12") (pinfunction "Y7_12") (pintype "tri_state"))
    )
    (net (code "151") (name "unconnected-(IC5A-Y8-Pad11)") (class "Default")
      (node (ref "IC5") (pin "11") (pinfunction "Y8_11") (pintype "tri_state"))
    )
    (net (code "152") (name "unconnected-(TFT-Pad2)") (class "Default")
      (node (ref "TFT") (pin "2") (pinfunction "2_2") (pintype "passive"))
    )
    (net (code "153") (name "unconnected-(TFT-Pad4)") (class "Default")
      (node (ref "TFT") (pin "4") (pinfunction "4_4") (pintype "passive"))
    )
    (net (code "154") (name "unconnected-(TFT-Pad5)") (class "Default")
      (node (ref "TFT") (pin "5") (pinfunction "5_5") (pintype "passive"))
    )
    (net (code "155") (name "unconnected-(TFT-Pad6)") (class "Default")
      (node (ref "TFT") (pin "6") (pinfunction "6_6") (pintype "passive"))
    )
    (net (code "156") (name "unconnected-(TFT-Pad8)") (class "Default")
      (node (ref "TFT") (pin "8") (pinfunction "8_8") (pintype "passive"))
    )
    (net (code "157") (name "unconnected-(TFT-Pad10)") (class "Default")
      (node (ref "TFT") (pin "10") (pinfunction "10_10") (pintype "passive"))
    )
    (net (code "158") (name "unconnected-(TFT-Pad12)") (class "Default")
      (node (ref "TFT") (pin "12") (pinfunction "12_12") (pintype "passive"))
    )
    (net (code "159") (name "unconnected-(TFT-Pad14)") (class "Default")
      (node (ref "TFT") (pin "14") (pinfunction "14_14") (pintype "passive"))
    )
    (net (code "160") (name "unconnected-(TFT-Pad16)") (class "Default")
      (node (ref "TFT") (pin "16") (pinfunction "16_16") (pintype "passive"))
    )
    (net (code "161") (name "unconnected-(TFT-Pad24)") (class "Default")
      (node (ref "TFT") (pin "24") (pinfunction "24_24") (pintype "passive"))
    )
    (net (code "162") (name "unconnected-(TFT-Pad31)") (class "Default")
      (node (ref "TFT") (pin "31") (pinfunction "31_31") (pintype "passive"))
    )
    (net (code "163") (name "unconnected-(TFT-Pad35)") (class "Default")
      (node (ref "TFT") (pin "35") (pinfunction "35_35") (pintype "passive"))
    )
    (net (code "164") (name "unconnected-(TFT-Pad38)") (class "Default")
      (node (ref "TFT") (pin "38") (pinfunction "38_38") (pintype "passive"))
    )
    (net (code "165") (name "unconnected-(TFT-Pad39)") (class "Default")
      (node (ref "TFT") (pin "39") (pinfunction "39_39") (pintype "passive"))
    )
    (net (code "166") (name "unconnected-(TFT-Pad40)") (class "Default")
      (node (ref "TFT") (pin "40") (pinfunction "40_40") (pintype "passive"))
    )
  )
)
